# encoder.net
KiCad netlist of a schematic drawn in EAGLE
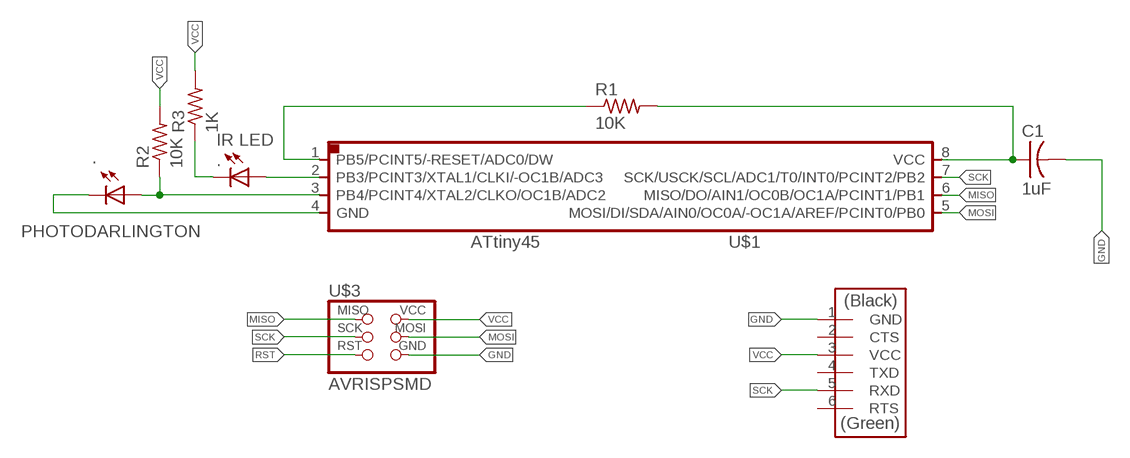
[diagram p0: schematic, sheet 1]

(export (version "E")
  (design (tool "Eeschema 10.0.6"))
  (components
    (comp (ref ".")
      (value "IR LED")
      (footprint "eagle-import:LED1206FAB")
      (libsource (lib "eagle-import") (part "LEDFAB1206"))
    )
    (comp (ref "C1")
      (value "1uF")
      (footprint "eagle-import:C1206FAB")
      (libsource (lib "eagle-import") (part "CAP-US1206FAB"))
    )
    (comp (ref "FTDI")
      (value "FTDI-SMD-HEADER")
      (footprint "eagle-import:1X06SMD")
      (libsource (lib "eagle-import") (part "FTDI-SMD-HEADER"))
    )
    (comp (ref "PHOTODARLINGTON")
      (value ".")
      (footprint "eagle-import:LED1206")
      (libsource (lib "eagle-import") (part "LED"))
    )
    (comp (ref "R1")
      (value "10K")
      (footprint "eagle-import:R1206FAB")
      (libsource (lib "eagle-import") (part "RES-US1206FAB"))
    )
    (comp (ref "R2")
      (value "10K")
      (footprint "eagle-import:R1206FAB")
      (libsource (lib "eagle-import") (part "RES-US1206FAB"))
    )
    (comp (ref "R3")
      (value "1K")
      (footprint "eagle-import:R1206FAB")
      (libsource (lib "eagle-import") (part "RES-US1206FAB"))
    )
    (comp (ref "U$1")
      (value "ATTINY45SI")
      (footprint "eagle-import:SOIC8")
      (libsource (lib "eagle-import") (part "ATTINY45SI"))
    )
    (comp (ref "U$3")
      (value "AVRISPSMD")
      (footprint "eagle-import:2X03SMD")
      (libsource (lib "eagle-import") (part "AVRISPSMD"))
    )
  )
  (nets
    (net (code "1") (name "GND") (class "Default")
      (node (ref "C1") (pin "2") (pinfunction "2_2") (pintype "passive"))
      (node (ref "FTDI") (pin "1") (pinfunction "GND_1") (pintype "bidirectional"))
      (node (ref "PHOTODARLINGTON") (pin "2") (pinfunction "C_2") (pintype "passive"))
      (node (ref "U$1") (pin "4") (pinfunction "GND_4") (pintype "bidirectional"))
      (node (ref "U$3") (pin "6") (pinfunction "GND_6") (pintype "passive"))
    )
    (net (code "2") (name "MISO") (class "Default")
      (node (ref "U$1") (pin "6") (pinfunction "MISO/DO/AIN1/OC0B/OC1A/PCINT1/PB1_6") (pintype "bidirectional"))
      (node (ref "U$3") (pin "1") (pinfunction "MISO_1") (pintype "passive"))
    )
    (net (code "3") (name "MOSI") (class "Default")
      (node (ref "U$1") (pin "5") (pinfunction "MOSI/DI/SDA/AIN0/OC0A/-OC1A/AREF/PCINT0/PB0_5") (pintype "bidirectional"))
      (node (ref "U$3") (pin "4") (pinfunction "MOSI_4") (pintype "passive"))
    )
    (net (code "4") (name "Net-(.-A)") (class "Default")
      (node (ref ".") (pin "1") (pinfunction "A_1") (pintype "passive"))
      (node (ref "U$1") (pin "2") (pinfunction "PB3/PCINT3/XTAL1/CLKI/-OC1B/ADC3_2") (pintype "bidirectional"))
    )
    (net (code "5") (name "Net-(.-C)") (class "Default")
      (node (ref ".") (pin "2") (pinfunction "C_2") (pintype "passive"))
      (node (ref "R3") (pin "1") (pinfunction "1_1") (pintype "passive"))
    )
    (net (code "6") (name "Net-(PHOTODARLINGTON-A)") (class "Default")
      (node (ref "PHOTODARLINGTON") (pin "1") (pinfunction "A_1") (pintype "passive"))
      (node (ref "R2") (pin "1") (pinfunction "1_1") (pintype "passive"))
      (node (ref "U$1") (pin "3") (pinfunction "PB4/PCINT4/XTAL2/CLKO/OC1B/ADC2_3") (pintype "bidirectional"))
    )
    (net (code "7") (name "RST") (class "Default")
      (node (ref "R1") (pin "1") (pinfunction "1_1") (pintype "passive"))
      (node (ref "U$1") (pin "1") (pinfunction "PB5/PCINT5/-RESET/ADC0/DW_1") (pintype "bidirectional"))
      (node (ref "U$3") (pin "5") (pinfunction "RST_5") (pintype "passive"))
    )
    (net (code "8") (name "SCK") (class "Default")
      (node (ref "FTDI") (pin "5") (pinfunction "RXD_5") (pintype "bidirectional"))
      (node (ref "U$1") (pin "7") (pinfunction "SCK/USCK/SCL/ADC1/T0/INT0/PCINT2/PB2_7") (pintype "bidirectional"))
      (node (ref "U$3") (pin "3") (pinfunction "SCK_3") (pintype "passive"))
    )
    (net (code "9") (name "VCC") (class "Default")
      (node (ref "C1") (pin "1") (pinfunction "1_1") (pintype "passive"))
      (node (ref "FTDI") (pin "3") (pinfunction "VCC_3") (pintype "bidirectional"))
      (node (ref "R1") (pin "2") (pinfunction "2_2") (pintype "passive"))
      (node (ref "R2") (pin "2") (pinfunction "2_2") (pintype "passive"))
      (node (ref "R3") (pin "2") (pinfunction "2_2") (pintype "passive"))
      (node (ref "U$1") (pin "8") (pinfunction "VCC_8") (pintype "bidirectional"))
      (node (ref "U$3") (pin "2") (pinfunction "VCC_2") (pintype "passive"))
    )
    (net (code "10") (name "unconnected-(FTDI-CTS-Pad2)") (class "Default")
      (node (ref "FTDI") (pin "2") (pinfunction "CTS_2") (pintype "bidirectional"))
    )
    (net (code "11") (name "unconnected-(FTDI-RTS-Pad6)") (class "Default")
      (node (ref "FTDI") (pin "6") (pinfunction "RTS_6") (pintype "bidirectional"))
    )
    (net (code "12") (name "unconnected-(FTDI-TXD-Pad4)") (class "Default")
      (node (ref "FTDI") (pin "4") (pinfunction "TXD_4") (pintype "bidirectional"))
    )
  )
)
